# boosst_revA.net
KiCad netlist of a schematic drawn in EAGLE
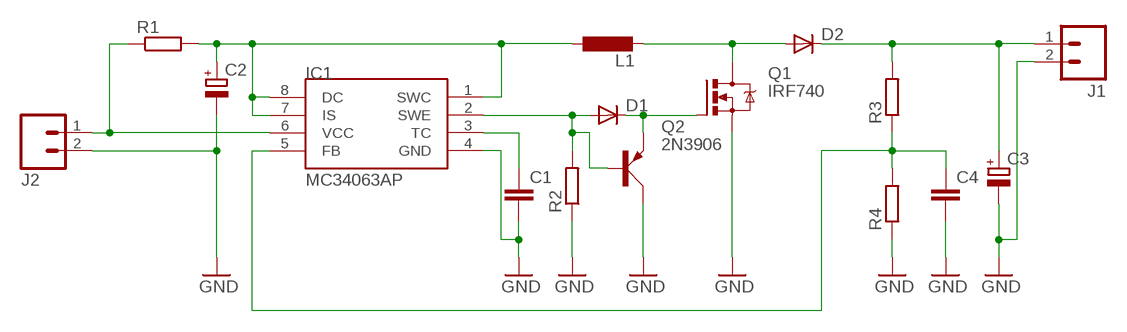
[diagram p0: schematic, sheet 1]

(export (version "E")
  (design (tool "Eeschema 10.0.6"))
  (components
    (comp (ref "C1")
      (value "C-EU025-025X050")
      (footprint "eagle-import:C025-025X050")
      (libsource (lib "eagle-import") (part "C-EU025-025X050"))
    )
    (comp (ref "C2")
      (value "CPOL-EUE5-8.5")
      (footprint "eagle-import:E5-8,5")
      (libsource (lib "eagle-import") (part "CPOL-EUE5-8.5"))
    )
    (comp (ref "C3")
      (value "CPOL-EUE5-8.5")
      (footprint "eagle-import:E5-8,5")
      (libsource (lib "eagle-import") (part "CPOL-EUE5-8.5"))
    )
    (comp (ref "C4")
      (value "C-EU025-025X050")
      (footprint "eagle-import:C025-025X050")
      (libsource (lib "eagle-import") (part "C-EU025-025X050"))
    )
    (comp (ref "D1")
      (value "DIODE-D-5")
      (footprint "eagle-import:D-5")
      (libsource (lib "eagle-import") (part "DIODE-D-5"))
    )
    (comp (ref "D2")
      (value "DIODE-DO41-7.6")
      (footprint "eagle-import:DO41-7.6")
      (libsource (lib "eagle-import") (part "DIODE-DO41-7.6"))
    )
    (comp (ref "IC1")
      (value "MC34063AP")
      (footprint "eagle-import:DIL08")
      (libsource (lib "eagle-import") (part "MC34063AP"))
    )
    (comp (ref "J1")
      (value "M023.5MM")
      (footprint "eagle-import:SCREWTERMINAL-3.5MM-2")
      (libsource (lib "eagle-import") (part "M023.5MM"))
    )
    (comp (ref "J2")
      (value "M023.5MM")
      (footprint "eagle-import:SCREWTERMINAL-3.5MM-2")
      (libsource (lib "eagle-import") (part "M023.5MM"))
    )
    (comp (ref "L1")
      (value "L-EU6000-XXX-RC")
      (footprint "eagle-import:6000-XXXX-RC")
      (libsource (lib "eagle-import") (part "L-EU6000-XXX-RC"))
    )
    (comp (ref "Q1")
      (value "IRF740")
      (footprint "eagle-import:TO220BV")
      (libsource (lib "eagle-import") (part "IRF740"))
    )
    (comp (ref "Q2")
      (value "2N3906")
      (footprint "eagle-import:TO92D")
      (libsource (lib "eagle-import") (part "2N3906"))
    )
    (comp (ref "R1")
      (value "R-EU_0309/10")
      (footprint "eagle-import:0309_10")
      (libsource (lib "eagle-import") (part "R-EU_0309/10"))
    )
    (comp (ref "R2")
      (value "R-EU_0204/5")
      (footprint "eagle-import:0204_5")
      (libsource (lib "eagle-import") (part "R-EU_0204/5"))
    )
    (comp (ref "R3")
      (value "R-EU_0204/7")
      (footprint "eagle-import:0204_7")
      (libsource (lib "eagle-import") (part "R-EU_0204/7"))
    )
    (comp (ref "R4")
      (value "R-EU_0204/7")
      (footprint "eagle-import:0204_7")
      (libsource (lib "eagle-import") (part "R-EU_0204/7"))
    )
  )
  (nets
    (net (code "1") (name "GND") (class "Default")
      (node (ref "C1") (pin "2") (pinfunction "2_2") (pintype "passive"))
      (node (ref "C2") (pin "-") (pinfunction "-_-") (pintype "passive"))
      (node (ref "C3") (pin "-") (pinfunction "-_-") (pintype "passive"))
      (node (ref "C4") (pin "2") (pinfunction "2_2") (pintype "passive"))
      (node (ref "IC1") (pin "4") (pinfunction "GND_4") (pintype "passive"))
      (node (ref "J1") (pin "2") (pinfunction "2_2") (pintype "passive"))
      (node (ref "J2") (pin "2") (pinfunction "2_2") (pintype "passive"))
      (node (ref "Q1") (pin "S") (pinfunction "S_S") (pintype "passive"))
      (node (ref "Q2") (pin "C") (pinfunction "C_C") (pintype "passive"))
      (node (ref "R2") (pin "1") (pinfunction "1_1") (pintype "passive"))
      (node (ref "R4") (pin "1") (pinfunction "1_1") (pintype "passive"))
    )
    (net (code "2") (name "Net-(C3-Pad+)") (class "Default")
      (node (ref "C3") (pin "+") (pinfunction "+_+") (pintype "passive"))
      (node (ref "D2") (pin "C") (pinfunction "C_C") (pintype "passive"))
      (node (ref "J1") (pin "1") (pinfunction "1_1") (pintype "passive"))
      (node (ref "R3") (pin "2") (pinfunction "2_2") (pintype "passive"))
    )
    (net (code "3") (name "Net-(D1-PadC)") (class "Default")
      (node (ref "D1") (pin "C") (pinfunction "C_C") (pintype "passive"))
      (node (ref "Q1") (pin "G") (pinfunction "G_G") (pintype "passive"))
      (node (ref "Q2") (pin "E") (pinfunction "E_E") (pintype "passive"))
    )
    (net (code "4") (name "Net-(D2-PadA)") (class "Default")
      (node (ref "D2") (pin "A") (pinfunction "A_A") (pintype "passive"))
      (node (ref "L1") (pin "2") (pinfunction "2_2") (pintype "passive"))
      (node (ref "Q1") (pin "D") (pinfunction "D_D") (pintype "passive"))
    )
    (net (code "5") (name "Net-(IC1-DC)") (class "Default")
      (node (ref "C2") (pin "+") (pinfunction "+_+") (pintype "passive"))
      (node (ref "IC1") (pin "1") (pinfunction "SWC_1") (pintype "passive"))
      (node (ref "IC1") (pin "7") (pinfunction "IS_7") (pintype "passive"))
      (node (ref "IC1") (pin "8") (pinfunction "DC_8") (pintype "passive"))
      (node (ref "L1") (pin "1") (pinfunction "1_1") (pintype "passive"))
      (node (ref "R1") (pin "2") (pinfunction "2_2") (pintype "passive"))
    )
    (net (code "6") (name "Net-(IC1-FB)") (class "Default")
      (node (ref "C4") (pin "1") (pinfunction "1_1") (pintype "passive"))
      (node (ref "IC1") (pin "5") (pinfunction "FB_5") (pintype "passive"))
      (node (ref "R3") (pin "1") (pinfunction "1_1") (pintype "passive"))
      (node (ref "R4") (pin "2") (pinfunction "2_2") (pintype "passive"))
    )
    (net (code "7") (name "Net-(IC1-SWE)") (class "Default")
      (node (ref "D1") (pin "A") (pinfunction "A_A") (pintype "passive"))
      (node (ref "IC1") (pin "2") (pinfunction "SWE_2") (pintype "passive"))
      (node (ref "Q2") (pin "B") (pinfunction "B_B") (pintype "passive"))
      (node (ref "R2") (pin "2") (pinfunction "2_2") (pintype "passive"))
    )
    (net (code "8") (name "Net-(IC1-TC)") (class "Default")
      (node (ref "C1") (pin "1") (pinfunction "1_1") (pintype "passive"))
      (node (ref "IC1") (pin "3") (pinfunction "TC_3") (pintype "passive"))
    )
    (net (code "9") (name "Net-(IC1-VCC)") (class "Default")
      (node (ref "IC1") (pin "6") (pinfunction "VCC_6") (pintype "passive"))
      (node (ref "J2") (pin "1") (pinfunction "1_1") (pintype "passive"))
      (node (ref "R1") (pin "1") (pinfunction "1_1") (pintype "passive"))
    )
  )
)
